# clock.net
KiCad netlist of a schematic drawn in Altium Designer
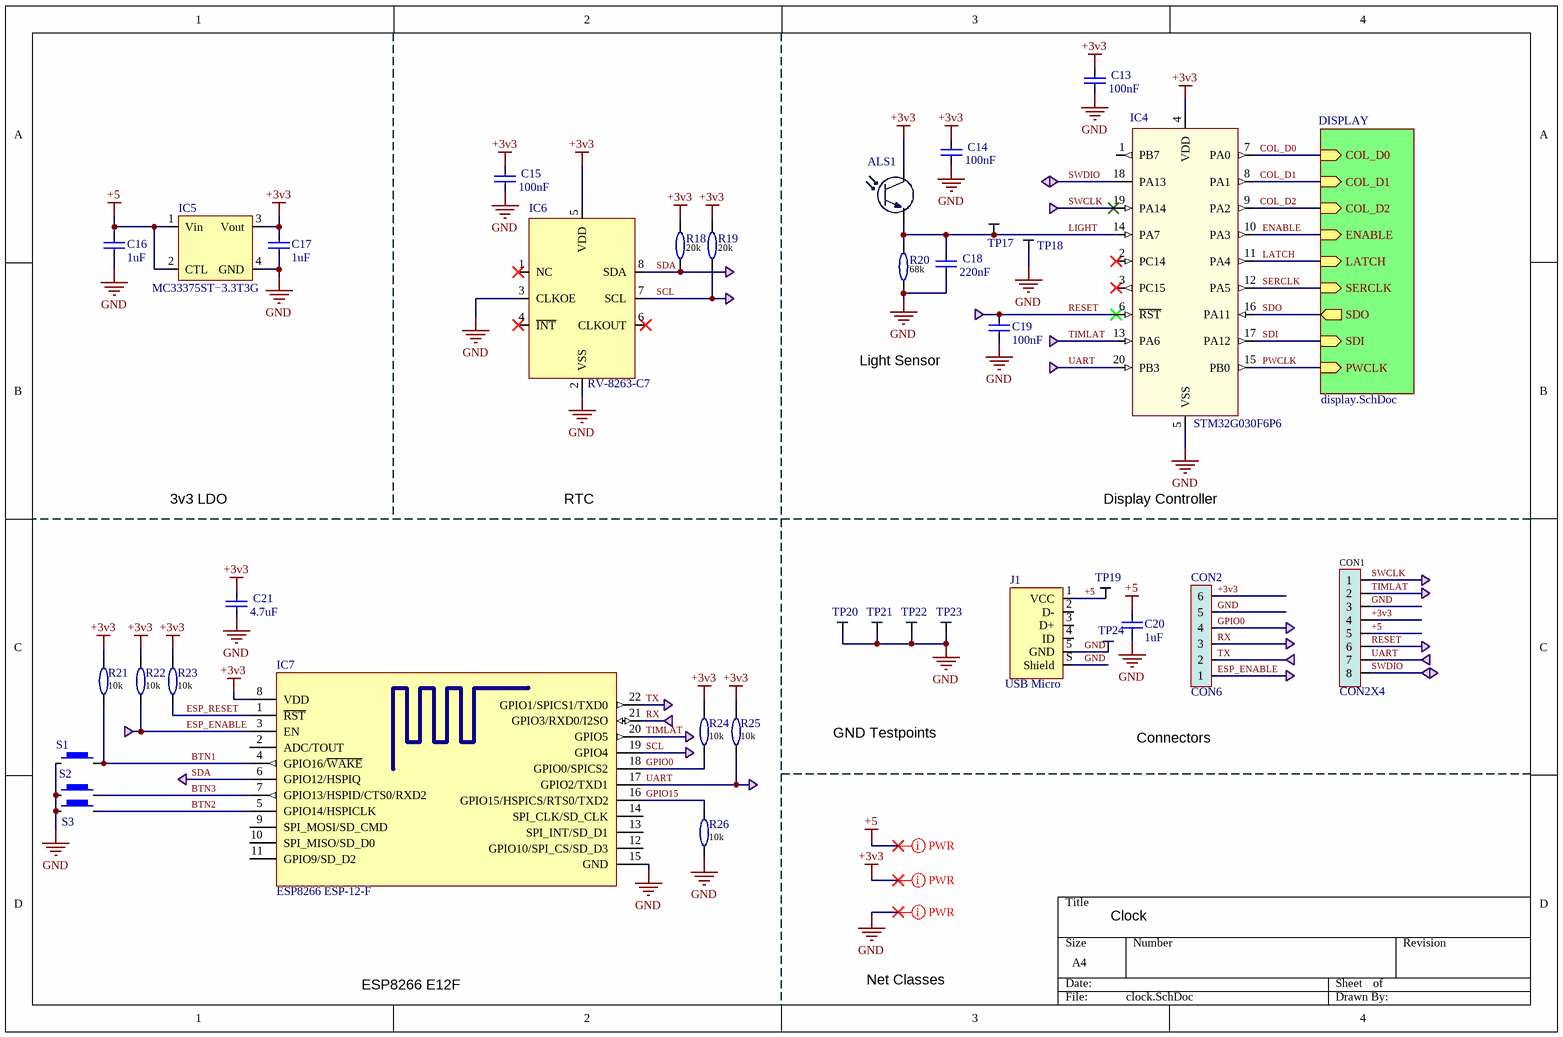
[diagram p0: clock.SchDoc]

(export (version "E")
  (design (tool "Eeschema 10.0.6"))
  (components
    (comp (ref "ALS1")
      (value "PHOTOTRANSISTOR")
      (footprint "ALS-PT19-315C")
      (description "Photo transistor")
      (libsource (lib "clock") (part "PHOTOTRANSISTOR"))
    )
    (comp (ref "C13")
      (value "100nF")
      (footprint "CAPC_0603_1608X08L")
      (description "Capacitor")
      (fields (field (name "Comment") "Cap") (field (name "PUBLISHER") "Altium Limited"))
      (libsource (lib "clock") (part "Cap"))
    )
    (comp (ref "C14")
      (value "100nF")
      (footprint "CAPC_0603_1608X08L")
      (description "Capacitor")
      (fields (field (name "Comment") "Cap") (field (name "PUBLISHER") "Altium Limited"))
      (libsource (lib "clock") (part "Cap"))
    )
    (comp (ref "C15")
      (value "100nF")
      (footprint "CAPC_0603_1608X08L")
      (description "Capacitor")
      (fields (field (name "Comment") "Cap") (field (name "PUBLISHER") "Altium Limited"))
      (libsource (lib "clock") (part "Cap"))
    )
    (comp (ref "C16")
      (value "1uF")
      (footprint "CAPC_0603_1608X08L")
      (description "Capacitor")
      (fields (field (name "Comment") "Cap") (field (name "PUBLISHER") "Altium Limited"))
      (libsource (lib "clock") (part "Cap"))
    )
    (comp (ref "C17")
      (value "1uF")
      (footprint "CAPC_0603_1608X08L")
      (description "Capacitor")
      (fields (field (name "Comment") "Cap") (field (name "PUBLISHER") "Altium Limited"))
      (libsource (lib "clock") (part "Cap"))
    )
    (comp (ref "C18")
      (value "220nF")
      (footprint "CAPC_0603_1608X08L")
      (description "Capacitor")
      (fields (field (name "Comment") "Cap") (field (name "PUBLISHER") "Altium Limited"))
      (libsource (lib "clock") (part "Cap"))
    )
    (comp (ref "C19")
      (value "100nF")
      (footprint "CAPC_0603_1608X08L")
      (description "Capacitor")
      (fields (field (name "Comment") "Cap") (field (name "PUBLISHER") "Altium Limited"))
      (libsource (lib "clock") (part "Cap"))
    )
    (comp (ref "C20")
      (value "1uF")
      (footprint "CAPC_1206_3216X16L")
      (description "Capacitor")
      (fields (field (name "Comment") "Cap") (field (name "PUBLISHER") "Altium Limited"))
      (libsource (lib "clock") (part "Cap"))
    )
    (comp (ref "C21")
      (value "4.7uF")
      (footprint "CAPC_1206_3216X16L")
      (description "Capacitor")
      (fields (field (name "Comment") "Cap") (field (name "PUBLISHER") "Altium Limited"))
      (libsource (lib "clock") (part "Cap"))
    )
    (comp (ref "CON1")
      (value "CON2X4")
      (footprint "CON2X4")
      (description "Header 4 way")
      (libsource (lib "clock") (part "CON2X4"))
    )
    (comp (ref "CON2")
      (value "CON6")
      (footprint "CON2X3")
      (description "Debug header 6 way")
      (libsource (lib "clock") (part "CON6"))
    )
    (comp (ref "IC4")
      (value "STM32G030F6P6")
      (footprint "TSOP65P630X120-20L")
      (description "MCU 64MHz tssop20")
      (libsource (lib "clock") (part "STM32G030F6P6"))
    )
    (comp (ref "IC5")
      (value "MC33375ST−3.3T3G")
      (footprint "SOT230P700X180-4N")
      (description "3.3v LDO")
      (libsource (lib "clock") (part "MC33375ST−3.3T3G"))
    )
    (comp (ref "IC6")
      (value "RV-8263-C7")
      (footprint "RV-8263-C7")
      (libsource (lib "clock") (part "RV-8263-C7"))
    )
    (comp (ref "IC7")
      (value "ESP8266 ESP-12-F")
      (footprint "ESP8266 ESP-12-E")
      (libsource (lib "clock") (part "ESP8266 ESP-12-F"))
    )
    (comp (ref "J1")
      (value "USB Micro")
      (footprint "USB 1051330011")
      (description "USB 2.0 Type B Micro vertical SMT")
      (libsource (lib "clock") (part "USB 2.0 Type B Micro"))
    )
    (comp (ref "R18")
      (value "20k")
      (footprint "RESC1608X03L")
      (description "Chip Resistor")
      (fields (field (name "Comment") "RES0603"))
      (libsource (lib "") (part "RES0603_1"))
    )
    (comp (ref "R19")
      (value "20k")
      (footprint "RESC1608X03L")
      (description "Chip Resistor")
      (fields (field (name "Comment") "RES0603"))
      (libsource (lib "") (part "RES0603_1"))
    )
    (comp (ref "R20")
      (value "68k")
      (footprint "RESC1608X03L")
      (description "Chip Resistor")
      (fields (field (name "Comment") "RES0603"))
      (libsource (lib "") (part "RES0603_1"))
    )
    (comp (ref "R21")
      (value "10k")
      (footprint "RESC1608X03L")
      (description "Chip Resistor")
      (fields (field (name "Comment") "RES0603"))
      (libsource (lib "clock") (part "RES0603"))
    )
    (comp (ref "R22")
      (value "10k")
      (footprint "RESC1608X03L")
      (description "Chip Resistor")
      (fields (field (name "Comment") "RES0603"))
      (libsource (lib "clock") (part "RES0603"))
    )
    (comp (ref "R23")
      (value "10k")
      (footprint "RESC1608X03L")
      (description "Chip Resistor")
      (fields (field (name "Comment") "RES0603"))
      (libsource (lib "clock") (part "RES0603"))
    )
    (comp (ref "R24")
      (value "10k")
      (footprint "RESC1608X03L")
      (description "Chip Resistor")
      (fields (field (name "Comment") "RES0603"))
      (libsource (lib "clock") (part "RES0603"))
    )
    (comp (ref "R25")
      (value "10k")
      (footprint "RESC1608X03L")
      (description "Chip Resistor")
      (fields (field (name "Comment") "RES0603"))
      (libsource (lib "clock") (part "RES0603"))
    )
    (comp (ref "R26")
      (value "10k")
      (footprint "RESC1608X03L")
      (description "Chip Resistor")
      (fields (field (name "Comment") "RES0603"))
      (libsource (lib "clock") (part "RES0603"))
    )
    (comp (ref "S1")
      (value "4-1437565-1")
      (footprint "FSM-SWITCH")
      (description "6x6mm SMD tactile switch,SPST-NO")
      (fields (field (name "RS PART NUMBER") "1616046"))
      (libsource (lib "clock") (part "tactile switch"))
    )
    (comp (ref "S2")
      (value "4-1437565-1")
      (footprint "FSM-SWITCH")
      (description "6x6mm SMD tactile switch,SPST-NO")
      (fields (field (name "RS PART NUMBER") "1616046"))
      (libsource (lib "clock") (part "tactile switch"))
    )
    (comp (ref "S3")
      (value "4-1437565-1")
      (footprint "FSM-SWITCH")
      (description "6x6mm SMD tactile switch,SPST-NO")
      (fields (field (name "RS PART NUMBER") "1616046"))
      (libsource (lib "clock") (part "tactile switch"))
    )
    (comp (ref "TP17")
      (value "TESTPOINT")
      (footprint "TESTPOINT_BIG")
      (libsource (lib "clock") (part "TESTPOINT"))
    )
    (comp (ref "TP18")
      (value "TESTPOINT")
      (footprint "TESTPOINT_GND")
      (libsource (lib "clock") (part "TESTPOINT"))
    )
    (comp (ref "TP19")
      (value "TESTPOINT")
      (footprint "TESTPOINT_BIG")
      (libsource (lib "clock") (part "TESTPOINT"))
    )
    (comp (ref "TP20")
      (value "TESTPOINT")
      (footprint "TESTPOINT_GND")
      (libsource (lib "clock") (part "TESTPOINT"))
    )
    (comp (ref "TP21")
      (value "TESTPOINT")
      (footprint "TESTPOINT_GND")
      (libsource (lib "clock") (part "TESTPOINT"))
    )
    (comp (ref "TP22")
      (value "TESTPOINT")
      (footprint "TESTPOINT_GND")
      (libsource (lib "clock") (part "TESTPOINT"))
    )
    (comp (ref "TP23")
      (value "TESTPOINT")
      (footprint "TESTPOINT_GND")
      (libsource (lib "clock") (part "TESTPOINT"))
    )
    (comp (ref "TP24")
      (value "TESTPOINT")
      (footprint "TESTPOINT_GND")
      (libsource (lib "clock") (part "TESTPOINT"))
    )
  )
  (nets
    (net (code "1") (name "+3v3") (class "Default")
      (node (ref "ALS1") (pin "1") (pinfunction "COLLECTOR_1") (pintype "power_in"))
      (node (ref "C13") (pin "2") (pinfunction "2_2") (pintype "passive"))
      (node (ref "C14") (pin "2") (pinfunction "2_2") (pintype "passive"))
      (node (ref "C15") (pin "2") (pinfunction "2_2") (pintype "passive"))
      (node (ref "C17") (pin "2") (pinfunction "2_2") (pintype "passive"))
      (node (ref "C21") (pin "2") (pinfunction "2_2") (pintype "passive"))
      (node (ref "CON1") (pin "4") (pinfunction "4_4") (pintype "passive"))
      (node (ref "CON2") (pin "6") (pinfunction "6_6") (pintype "passive"))
      (node (ref "IC4") (pin "4") (pinfunction "VDD_4") (pintype "power_in"))
      (node (ref "IC5") (pin "3") (pinfunction "Vout_3") (pintype "passive"))
      (node (ref "IC6") (pin "5") (pinfunction "VDD_5") (pintype "power_in"))
      (node (ref "IC7") (pin "8") (pinfunction "VDD_8") (pintype "passive"))
      (node (ref "R18") (pin "2") (pinfunction "2_2") (pintype "passive"))
      (node (ref "R19") (pin "2") (pinfunction "2_2") (pintype "passive"))
      (node (ref "R21") (pin "1") (pinfunction "1_1") (pintype "passive"))
      (node (ref "R22") (pin "1") (pinfunction "1_1") (pintype "passive"))
      (node (ref "R23") (pin "1") (pinfunction "1_1") (pintype "passive"))
      (node (ref "R24") (pin "1") (pinfunction "1_1") (pintype "passive"))
      (node (ref "R25") (pin "1") (pinfunction "1_1") (pintype "passive"))
    )
    (net (code "2") (name "+5") (class "Default")
      (node (ref "C16") (pin "2") (pinfunction "2_2") (pintype "passive"))
      (node (ref "C20") (pin "2") (pinfunction "2_2") (pintype "passive"))
      (node (ref "CON1") (pin "5") (pinfunction "5_5") (pintype "passive"))
      (node (ref "IC5") (pin "1") (pinfunction "Vin_1") (pintype "passive"))
      (node (ref "IC5") (pin "2") (pinfunction "CTL_2") (pintype "passive"))
      (node (ref "J1") (pin "1") (pinfunction "VCC_1") (pintype "passive"))
      (node (ref "TP19") (pin "1") (pinfunction "EMITTER_1") (pintype "power_in"))
    )
    (net (code "3") (name "/BTN1") (class "Default")
      (node (ref "IC7") (pin "4") (pinfunction "GPIO16/~{WAKE}_4") (pintype "output"))
      (node (ref "R21") (pin "2") (pinfunction "2_2") (pintype "passive"))
      (node (ref "S1") (pin "2") (pinfunction "2_2") (pintype "passive"))
    )
    (net (code "4") (name "/BTN2") (class "Default")
      (node (ref "IC7") (pin "5") (pinfunction "GPIO14/HSPICLK_5") (pintype "open_emitter"))
      (node (ref "S3") (pin "2") (pinfunction "2_2") (pintype "passive"))
    )
    (net (code "5") (name "/BTN3") (class "Default")
      (node (ref "IC7") (pin "7") (pinfunction "GPIO13/HSPID/CTS0/RXD2_7") (pintype "output"))
      (node (ref "S2") (pin "2") (pinfunction "2_2") (pintype "passive"))
    )
    (net (code "6") (name "/COL_D0") (class "Default")
      (node (ref "IC4") (pin "7") (pinfunction "PA0_7") (pintype "output"))
    )
    (net (code "7") (name "/COL_D1") (class "Default")
      (node (ref "IC4") (pin "8") (pinfunction "PA1_8") (pintype "output"))
    )
    (net (code "8") (name "/COL_D2") (class "Default")
      (node (ref "IC4") (pin "9") (pinfunction "PA2_9") (pintype "output"))
    )
    (net (code "9") (name "/ENABLE") (class "Default")
      (node (ref "IC4") (pin "10") (pinfunction "PA3_10") (pintype "output"))
    )
    (net (code "10") (name "/ESP_ENABLE") (class "Default")
      (node (ref "CON2") (pin "1") (pinfunction "1_1") (pintype "passive"))
      (node (ref "IC7") (pin "3") (pinfunction "EN_3") (pintype "passive"))
      (node (ref "R22") (pin "2") (pinfunction "2_2") (pintype "passive"))
    )
    (net (code "11") (name "/ESP_RESET") (class "Default")
      (node (ref "IC7") (pin "1") (pinfunction "~{RST}_1") (pintype "passive"))
      (node (ref "R23") (pin "2") (pinfunction "2_2") (pintype "passive"))
    )
    (net (code "12") (name "/GPIO0") (class "Default")
      (node (ref "CON2") (pin "4") (pinfunction "4_4") (pintype "passive"))
      (node (ref "IC7") (pin "18") (pinfunction "GPIO0/SPICS2_18") (pintype "open_collector"))
      (node (ref "R24") (pin "2") (pinfunction "2_2") (pintype "passive"))
    )
    (net (code "13") (name "/GPIO15") (class "Default")
      (node (ref "IC7") (pin "16") (pinfunction "GPIO15/HSPICS/RTS0/TXD2_16") (pintype "open_emitter"))
      (node (ref "R26") (pin "1") (pinfunction "1_1") (pintype "passive"))
    )
    (net (code "14") (name "/LATCH") (class "Default")
      (node (ref "IC4") (pin "11") (pinfunction "PA4_11") (pintype "output"))
    )
    (net (code "15") (name "/LIGHT") (class "Default")
      (node (ref "ALS1") (pin "2") (pinfunction "EMITTER_2") (pintype "power_in"))
      (node (ref "C18") (pin "2") (pinfunction "2_2") (pintype "passive"))
      (node (ref "IC4") (pin "14") (pinfunction "PA7_14") (pintype "input"))
      (node (ref "R20") (pin "2") (pinfunction "2_2") (pintype "passive"))
      (node (ref "TP17") (pin "1") (pinfunction "EMITTER_1") (pintype "power_in"))
    )
    (net (code "16") (name "/PWCLK") (class "Default")
      (node (ref "IC4") (pin "15") (pinfunction "PB0_15") (pintype "output"))
    )
    (net (code "17") (name "/RESET") (class "Default")
      (node (ref "C19") (pin "2") (pinfunction "2_2") (pintype "passive"))
      (node (ref "CON1") (pin "6") (pinfunction "6_6") (pintype "passive"))
      (node (ref "IC4") (pin "6") (pinfunction "RST_6") (pintype "input"))
    )
    (net (code "18") (name "/RX") (class "Default")
      (node (ref "CON2") (pin "3") (pinfunction "3_3") (pintype "passive"))
      (node (ref "IC7") (pin "21") (pinfunction "GPIO3/RXD0/I2SO_21") (pintype "bidirectional"))
    )
    (net (code "19") (name "/SCL") (class "Default")
      (node (ref "IC6") (pin "7") (pinfunction "SCL_7") (pintype "open_emitter"))
      (node (ref "IC7") (pin "19") (pinfunction "GPIO4_19") (pintype "open_emitter"))
      (node (ref "R19") (pin "1") (pinfunction "1_1") (pintype "passive"))
    )
    (net (code "20") (name "/SDA") (class "Default")
      (node (ref "IC6") (pin "8") (pinfunction "SDA_8") (pintype "open_emitter"))
      (node (ref "IC7") (pin "6") (pinfunction "GPIO12/HSPIQ_6") (pintype "open_emitter"))
      (node (ref "R18") (pin "1") (pinfunction "1_1") (pintype "passive"))
    )
    (net (code "21") (name "/SDI") (class "Default")
      (node (ref "IC4") (pin "17") (pinfunction "PA12_17") (pintype "output"))
    )
    (net (code "22") (name "/SDO") (class "Default")
      (node (ref "IC4") (pin "16") (pinfunction "PA11_16") (pintype "input"))
    )
    (net (code "23") (name "/SERCLK") (class "Default")
      (node (ref "IC4") (pin "12") (pinfunction "PA5_12") (pintype "output"))
    )
    (net (code "24") (name "/SWCLK") (class "Default")
      (node (ref "CON1") (pin "1") (pinfunction "1_1") (pintype "passive"))
      (node (ref "IC4") (pin "19") (pinfunction "PA14_19") (pintype "input"))
    )
    (net (code "25") (name "/SWDIO") (class "Default")
      (node (ref "CON1") (pin "8") (pinfunction "8_8") (pintype "passive"))
      (node (ref "IC4") (pin "18") (pinfunction "PA13_18") (pintype "bidirectional"))
    )
    (net (code "26") (name "/TIMLAT") (class "Default")
      (node (ref "CON1") (pin "2") (pinfunction "2_2") (pintype "passive"))
      (node (ref "IC4") (pin "13") (pinfunction "PA6_13") (pintype "input"))
      (node (ref "IC7") (pin "20") (pinfunction "GPIO5_20") (pintype "output"))
    )
    (net (code "27") (name "/TX") (class "Default")
      (node (ref "CON2") (pin "2") (pinfunction "2_2") (pintype "passive"))
      (node (ref "IC7") (pin "22") (pinfunction "GPIO1/SPICS1/TXD0_22") (pintype "output"))
    )
    (net (code "28") (name "/UART") (class "Default")
      (node (ref "CON1") (pin "7") (pinfunction "7_7") (pintype "passive"))
      (node (ref "IC4") (pin "20") (pinfunction "PB3_20") (pintype "input"))
      (node (ref "IC7") (pin "17") (pinfunction "GPIO2/TXD1_17") (pintype "open_collector"))
      (node (ref "R25") (pin "2") (pinfunction "2_2") (pintype "passive"))
    )
    (net (code "29") (name "GND") (class "Default")
      (node (ref "C13") (pin "1") (pinfunction "1_1") (pintype "passive"))
      (node (ref "C14") (pin "1") (pinfunction "1_1") (pintype "passive"))
      (node (ref "C15") (pin "1") (pinfunction "1_1") (pintype "passive"))
      (node (ref "C16") (pin "1") (pinfunction "1_1") (pintype "passive"))
      (node (ref "C17") (pin "1") (pinfunction "1_1") (pintype "passive"))
      (node (ref "C18") (pin "1") (pinfunction "1_1") (pintype "passive"))
      (node (ref "C19") (pin "1") (pinfunction "1_1") (pintype "passive"))
      (node (ref "C20") (pin "1") (pinfunction "1_1") (pintype "passive"))
      (node (ref "C21") (pin "1") (pinfunction "1_1") (pintype "passive"))
      (node (ref "CON1") (pin "3") (pinfunction "3_3") (pintype "passive"))
      (node (ref "CON2") (pin "5") (pinfunction "5_5") (pintype "passive"))
      (node (ref "IC4") (pin "5") (pinfunction "VSS_5") (pintype "power_in"))
      (node (ref "IC5") (pin "4") (pinfunction "GND_4") (pintype "passive"))
      (node (ref "IC6") (pin "2") (pinfunction "VSS_2") (pintype "power_in"))
      (node (ref "IC6") (pin "3") (pinfunction "CLKOE_3") (pintype "input"))
      (node (ref "IC7") (pin "15") (pinfunction "GND_15") (pintype "passive"))
      (node (ref "J1") (pin "5") (pinfunction "GND_5") (pintype "passive"))
      (node (ref "J1") (pin "S") (pinfunction "Shield_S") (pintype "passive"))
      (node (ref "R20") (pin "1") (pinfunction "1_1") (pintype "passive"))
      (node (ref "R26") (pin "2") (pinfunction "2_2") (pintype "passive"))
      (node (ref "S1") (pin "1") (pinfunction "1_1") (pintype "passive"))
      (node (ref "S2") (pin "1") (pinfunction "1_1") (pintype "passive"))
      (node (ref "S3") (pin "1") (pinfunction "1_1") (pintype "passive"))
      (node (ref "TP18") (pin "1") (pinfunction "EMITTER_1") (pintype "power_in"))
      (node (ref "TP20") (pin "1") (pinfunction "EMITTER_1") (pintype "power_in"))
      (node (ref "TP21") (pin "1") (pinfunction "EMITTER_1") (pintype "power_in"))
      (node (ref "TP22") (pin "1") (pinfunction "EMITTER_1") (pintype "power_in"))
      (node (ref "TP23") (pin "1") (pinfunction "EMITTER_1") (pintype "power_in"))
      (node (ref "TP24") (pin "1") (pinfunction "EMITTER_1") (pintype "power_in"))
    )
    (net (code "30") (name "unconnected-(IC4-PB7-Pad1)") (class "Default")
      (node (ref "IC4") (pin "1") (pinfunction "PB7_1") (pintype "output"))
    )
    (net (code "31") (name "unconnected-(IC4-PC14-Pad2)") (class "Default")
      (node (ref "IC4") (pin "2") (pinfunction "PC14_2") (pintype "input+no_connect"))
    )
    (net (code "32") (name "unconnected-(IC4-PC15-Pad3)") (class "Default")
      (node (ref "IC4") (pin "3") (pinfunction "PC15_3") (pintype "output+no_connect"))
    )
    (net (code "33") (name "unconnected-(IC6-CLKOUT-Pad6)") (class "Default")
      (node (ref "IC6") (pin "6") (pinfunction "CLKOUT_6") (pintype "output+no_connect"))
    )
    (net (code "34") (name "unconnected-(IC6-INT-Pad4)") (class "Default")
      (node (ref "IC6") (pin "4") (pinfunction "INT_4") (pintype "output+no_connect"))
    )
    (net (code "35") (name "unconnected-(IC6-NC-Pad1)") (class "Default")
      (node (ref "IC6") (pin "1") (pinfunction "NC_1") (pintype "passive+no_connect"))
    )
    (net (code "36") (name "unconnected-(IC7-ADC{slash}TOUT-Pad2)") (class "Default")
      (node (ref "IC7") (pin "2") (pinfunction "ADC/TOUT_2") (pintype "passive"))
    )
    (net (code "37") (name "unconnected-(IC7-GPIO9{slash}SD_D2-Pad11)") (class "Default")
      (node (ref "IC7") (pin "11") (pinfunction "GPIO9/SD_D2_11") (pintype "passive"))
    )
    (net (code "38") (name "unconnected-(IC7-GPIO10{slash}SPI_CS{slash}SD_D3-Pad12)") (class "Default")
      (node (ref "IC7") (pin "12") (pinfunction "GPIO10/SPI_CS/SD_D3_12") (pintype "passive"))
    )
    (net (code "39") (name "unconnected-(IC7-SPI_CLK{slash}SD_CLK-Pad14)") (class "Default")
      (node (ref "IC7") (pin "14") (pinfunction "SPI_CLK/SD_CLK_14") (pintype "passive"))
    )
    (net (code "40") (name "unconnected-(IC7-SPI_INT{slash}SD_D1-Pad13)") (class "Default")
      (node (ref "IC7") (pin "13") (pinfunction "SPI_INT/SD_D1_13") (pintype "passive"))
    )
    (net (code "41") (name "unconnected-(IC7-SPI_MISO{slash}SD_D0-Pad10)") (class "Default")
      (node (ref "IC7") (pin "10") (pinfunction "SPI_MISO/SD_D0_10") (pintype "passive"))
    )
    (net (code "42") (name "unconnected-(IC7-SPI_MOSI{slash}SD_CMD-Pad9)") (class "Default")
      (node (ref "IC7") (pin "9") (pinfunction "SPI_MOSI/SD_CMD_9") (pintype "passive"))
    )
    (net (code "43") (name "unconnected-(J1-D+-Pad3)") (class "Default")
      (node (ref "J1") (pin "3") (pinfunction "D+_3") (pintype "passive"))
    )
    (net (code "44") (name "unconnected-(J1-D--Pad2)") (class "Default")
      (node (ref "J1") (pin "2") (pinfunction "D-_2") (pintype "passive"))
    )
    (net (code "45") (name "unconnected-(J1-ID-Pad4)") (class "Default")
      (node (ref "J1") (pin "4") (pinfunction "ID_4") (pintype "passive"))
    )
  )
)
